# PGTN034_quantizer_mki_panel.net
KiCad netlist of a schematic drawn in EAGLE
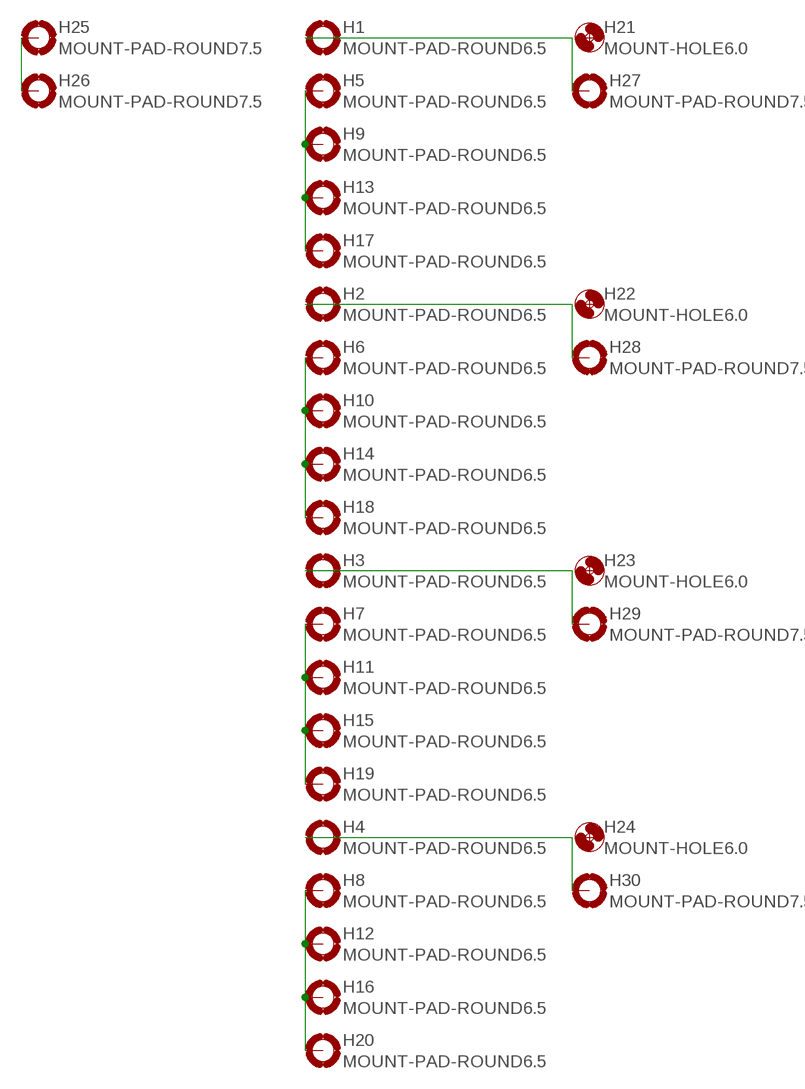
[diagram p0: schematic, sheet 1]

(export (version "E")
  (design (tool "Eeschema 10.0.6"))
  (components
    (comp (ref "H1")
      (value "MOUNT-PAD-ROUND6.5")
      (footprint "eagle-import:6.5-PAD")
      (libsource (lib "eagle-import") (part "MOUNT-PAD-ROUND6.5"))
    )
    (comp (ref "H2")
      (value "MOUNT-PAD-ROUND6.5")
      (footprint "eagle-import:6.5-PAD")
      (libsource (lib "eagle-import") (part "MOUNT-PAD-ROUND6.5"))
    )
    (comp (ref "H3")
      (value "MOUNT-PAD-ROUND6.5")
      (footprint "eagle-import:6.5-PAD")
      (libsource (lib "eagle-import") (part "MOUNT-PAD-ROUND6.5"))
    )
    (comp (ref "H4")
      (value "MOUNT-PAD-ROUND6.5")
      (footprint "eagle-import:6.5-PAD")
      (libsource (lib "eagle-import") (part "MOUNT-PAD-ROUND6.5"))
    )
    (comp (ref "H5")
      (value "MOUNT-PAD-ROUND6.5")
      (footprint "eagle-import:6.5-PAD")
      (libsource (lib "eagle-import") (part "MOUNT-PAD-ROUND6.5"))
    )
    (comp (ref "H6")
      (value "MOUNT-PAD-ROUND6.5")
      (footprint "eagle-import:6.5-PAD")
      (libsource (lib "eagle-import") (part "MOUNT-PAD-ROUND6.5"))
    )
    (comp (ref "H7")
      (value "MOUNT-PAD-ROUND6.5")
      (footprint "eagle-import:6.5-PAD")
      (libsource (lib "eagle-import") (part "MOUNT-PAD-ROUND6.5"))
    )
    (comp (ref "H8")
      (value "MOUNT-PAD-ROUND6.5")
      (footprint "eagle-import:6.5-PAD")
      (libsource (lib "eagle-import") (part "MOUNT-PAD-ROUND6.5"))
    )
    (comp (ref "H9")
      (value "MOUNT-PAD-ROUND6.5")
      (footprint "eagle-import:6.5-PAD")
      (libsource (lib "eagle-import") (part "MOUNT-PAD-ROUND6.5"))
    )
    (comp (ref "H10")
      (value "MOUNT-PAD-ROUND6.5")
      (footprint "eagle-import:6.5-PAD")
      (libsource (lib "eagle-import") (part "MOUNT-PAD-ROUND6.5"))
    )
    (comp (ref "H11")
      (value "MOUNT-PAD-ROUND6.5")
      (footprint "eagle-import:6.5-PAD")
      (libsource (lib "eagle-import") (part "MOUNT-PAD-ROUND6.5"))
    )
    (comp (ref "H12")
      (value "MOUNT-PAD-ROUND6.5")
      (footprint "eagle-import:6.5-PAD")
      (libsource (lib "eagle-import") (part "MOUNT-PAD-ROUND6.5"))
    )
    (comp (ref "H13")
      (value "MOUNT-PAD-ROUND6.5")
      (footprint "eagle-import:6.5-PAD")
      (libsource (lib "eagle-import") (part "MOUNT-PAD-ROUND6.5"))
    )
    (comp (ref "H14")
      (value "MOUNT-PAD-ROUND6.5")
      (footprint "eagle-import:6.5-PAD")
      (libsource (lib "eagle-import") (part "MOUNT-PAD-ROUND6.5"))
    )
    (comp (ref "H15")
      (value "MOUNT-PAD-ROUND6.5")
      (footprint "eagle-import:6.5-PAD")
      (libsource (lib "eagle-import") (part "MOUNT-PAD-ROUND6.5"))
    )
    (comp (ref "H16")
      (value "MOUNT-PAD-ROUND6.5")
      (footprint "eagle-import:6.5-PAD")
      (libsource (lib "eagle-import") (part "MOUNT-PAD-ROUND6.5"))
    )
    (comp (ref "H17")
      (value "MOUNT-PAD-ROUND6.5")
      (footprint "eagle-import:6.5-PAD")
      (libsource (lib "eagle-import") (part "MOUNT-PAD-ROUND6.5"))
    )
    (comp (ref "H18")
      (value "MOUNT-PAD-ROUND6.5")
      (footprint "eagle-import:6.5-PAD")
      (libsource (lib "eagle-import") (part "MOUNT-PAD-ROUND6.5"))
    )
    (comp (ref "H19")
      (value "MOUNT-PAD-ROUND6.5")
      (footprint "eagle-import:6.5-PAD")
      (libsource (lib "eagle-import") (part "MOUNT-PAD-ROUND6.5"))
    )
    (comp (ref "H20")
      (value "MOUNT-PAD-ROUND6.5")
      (footprint "eagle-import:6.5-PAD")
      (libsource (lib "eagle-import") (part "MOUNT-PAD-ROUND6.5"))
    )
    (comp (ref "H21")
      (value "MOUNT-HOLE6.0")
      (footprint "eagle-import:6,0")
      (libsource (lib "eagle-import") (part "MOUNT-HOLE6.0"))
    )
    (comp (ref "H22")
      (value "MOUNT-HOLE6.0")
      (footprint "eagle-import:6,0")
      (libsource (lib "eagle-import") (part "MOUNT-HOLE6.0"))
    )
    (comp (ref "H23")
      (value "MOUNT-HOLE6.0")
      (footprint "eagle-import:6,0")
      (libsource (lib "eagle-import") (part "MOUNT-HOLE6.0"))
    )
    (comp (ref "H24")
      (value "MOUNT-HOLE6.0")
      (footprint "eagle-import:6,0")
      (libsource (lib "eagle-import") (part "MOUNT-HOLE6.0"))
    )
    (comp (ref "H25")
      (value "MOUNT-PAD-ROUND7.5")
      (footprint "eagle-import:7.5-PAD")
      (libsource (lib "eagle-import") (part "MOUNT-PAD-ROUND7.5"))
    )
    (comp (ref "H26")
      (value "MOUNT-PAD-ROUND7.5")
      (footprint "eagle-import:7.5-PAD")
      (libsource (lib "eagle-import") (part "MOUNT-PAD-ROUND7.5"))
    )
    (comp (ref "H27")
      (value "MOUNT-PAD-ROUND7.5")
      (footprint "eagle-import:7.5-PAD")
      (libsource (lib "eagle-import") (part "MOUNT-PAD-ROUND7.5"))
    )
    (comp (ref "H28")
      (value "MOUNT-PAD-ROUND7.5")
      (footprint "eagle-import:7.5-PAD")
      (libsource (lib "eagle-import") (part "MOUNT-PAD-ROUND7.5"))
    )
    (comp (ref "H29")
      (value "MOUNT-PAD-ROUND7.5")
      (footprint "eagle-import:7.5-PAD")
      (libsource (lib "eagle-import") (part "MOUNT-PAD-ROUND7.5"))
    )
    (comp (ref "H30")
      (value "MOUNT-PAD-ROUND7.5")
      (footprint "eagle-import:7.5-PAD")
      (libsource (lib "eagle-import") (part "MOUNT-PAD-ROUND7.5"))
    )
  )
  (nets
    (net (code "1") (name "Net-(H1-MOUNT)") (class "Default")
      (node (ref "H1") (pin "B6.5") (pinfunction "MOUNT_B6.5") (pintype "passive"))
      (node (ref "H27") (pin "B7.5") (pinfunction "MOUNT_B7.5") (pintype "passive"))
    )
    (net (code "2") (name "Net-(H2-MOUNT)") (class "Default")
      (node (ref "H2") (pin "B6.5") (pinfunction "MOUNT_B6.5") (pintype "passive"))
      (node (ref "H28") (pin "B7.5") (pinfunction "MOUNT_B7.5") (pintype "passive"))
    )
    (net (code "3") (name "Net-(H10-MOUNT)") (class "Default")
      (node (ref "H10") (pin "B6.5") (pinfunction "MOUNT_B6.5") (pintype "passive"))
      (node (ref "H14") (pin "B6.5") (pinfunction "MOUNT_B6.5") (pintype "passive"))
      (node (ref "H18") (pin "B6.5") (pinfunction "MOUNT_B6.5") (pintype "passive"))
      (node (ref "H6") (pin "B6.5") (pinfunction "MOUNT_B6.5") (pintype "passive"))
    )
    (net (code "4") (name "Net-(H11-MOUNT)") (class "Default")
      (node (ref "H11") (pin "B6.5") (pinfunction "MOUNT_B6.5") (pintype "passive"))
      (node (ref "H15") (pin "B6.5") (pinfunction "MOUNT_B6.5") (pintype "passive"))
      (node (ref "H19") (pin "B6.5") (pinfunction "MOUNT_B6.5") (pintype "passive"))
      (node (ref "H7") (pin "B6.5") (pinfunction "MOUNT_B6.5") (pintype "passive"))
    )
    (net (code "5") (name "Net-(H12-MOUNT)") (class "Default")
      (node (ref "H12") (pin "B6.5") (pinfunction "MOUNT_B6.5") (pintype "passive"))
      (node (ref "H16") (pin "B6.5") (pinfunction "MOUNT_B6.5") (pintype "passive"))
      (node (ref "H20") (pin "B6.5") (pinfunction "MOUNT_B6.5") (pintype "passive"))
      (node (ref "H8") (pin "B6.5") (pinfunction "MOUNT_B6.5") (pintype "passive"))
    )
    (net (code "6") (name "Net-(H13-MOUNT)") (class "Default")
      (node (ref "H13") (pin "B6.5") (pinfunction "MOUNT_B6.5") (pintype "passive"))
      (node (ref "H17") (pin "B6.5") (pinfunction "MOUNT_B6.5") (pintype "passive"))
      (node (ref "H5") (pin "B6.5") (pinfunction "MOUNT_B6.5") (pintype "passive"))
      (node (ref "H9") (pin "B6.5") (pinfunction "MOUNT_B6.5") (pintype "passive"))
    )
    (net (code "7") (name "Net-(H25-MOUNT)") (class "Default")
      (node (ref "H25") (pin "B7.5") (pinfunction "MOUNT_B7.5") (pintype "passive"))
      (node (ref "H26") (pin "B7.5") (pinfunction "MOUNT_B7.5") (pintype "passive"))
    )
    (net (code "8") (name "Net-(H29-MOUNT)") (class "Default")
      (node (ref "H29") (pin "B7.5") (pinfunction "MOUNT_B7.5") (pintype "passive"))
      (node (ref "H3") (pin "B6.5") (pinfunction "MOUNT_B6.5") (pintype "passive"))
    )
    (net (code "9") (name "Net-(H30-MOUNT)") (class "Default")
      (node (ref "H30") (pin "B7.5") (pinfunction "MOUNT_B7.5") (pintype "passive"))
      (node (ref "H4") (pin "B6.5") (pinfunction "MOUNT_B6.5") (pintype "passive"))
    )
  )
)
